# LC_LPF11.net
KiCad netlist of a schematic drawn in Altium Designer
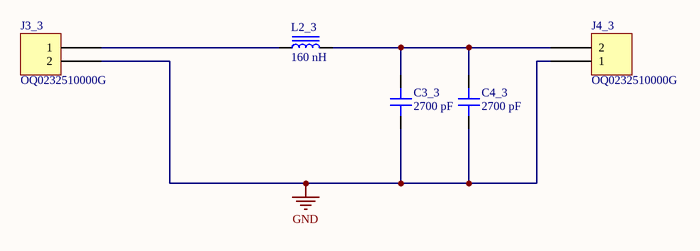
[diagram p0: LC_LPF11.SchDoc]

(export (version "E")
  (design (tool "Eeschema 10.0.6"))
  (components
    (comp (ref "C3_3")
      (value "2700 pF")
      (footprint "CAP 0603_1608")
      (description "CAP CER 2700PF 25V NP0 0603")
      (fields (field (name "PART NUMBER") "C0603C272F3GAC7867") (field (name "MANUFACTURER") "KEMET"))
      (libsource (lib "Celestial Altium Library - altium_library") (part "Capacitor"))
    )
    (comp (ref "C4_3")
      (value "2700 pF")
      (footprint "CAP 0603_1608")
      (description "CAP CER 2700PF 25V NP0 0603")
      (fields (field (name "PART NUMBER") "C0603C272F3GAC7867") (field (name "MANUFACTURER") "KEMET"))
      (libsource (lib "Celestial Altium Library - altium_library") (part "Capacitor"))
    )
    (comp (ref "J3_3")
      (value "OQ0232510000G")
      (footprint "FCI 06-381-2PIN")
      (description "TERM BLOCK HDR 2POS 90DEG 3.81MM")
      (fields (field (name "MANUFACTURER") "Amphenol Anytek"))
      (libsource (lib "Celestial Altium Library - altium_library") (part "2 Pin"))
    )
    (comp (ref "J4_3")
      (value "OQ0232510000G")
      (footprint "FCI 06-381-2PIN")
      (description "TERM BLOCK HDR 2POS 90DEG 3.81MM")
      (fields (field (name "MANUFACTURER") "Amphenol Anytek"))
      (libsource (lib "") (part "2 Pin_1"))
    )
    (comp (ref "L2_3")
      (value "160 nH")
      (footprint "IND 0402_1005 RF WW")
      (description "FIXED IND 160NH 480MA 330MOHM SM")
      (fields
        (field (name "PART NUMBER") "LQW15CNR16J00D")
        (field (name "MANUFACTURER") "Murata Electronics")
      )
      (libsource (lib "Celestial Altium Library - altium_library") (part "Inductor"))
    )
  )
  (nets
    (net (code "1") (name "GND") (class "Default")
      (node (ref "C3_3") (pin "1") (pinfunction "1_1") (pintype "passive"))
      (node (ref "C4_3") (pin "1") (pinfunction "1_1") (pintype "passive"))
      (node (ref "J3_3") (pin "2") (pinfunction "2_2") (pintype "passive"))
      (node (ref "J4_3") (pin "1") (pinfunction "1_1") (pintype "passive"))
    )
    (net (code "2") (name "Net-(C3_3-Pad2)") (class "Default")
      (node (ref "C3_3") (pin "2") (pinfunction "2_2") (pintype "passive"))
      (node (ref "C4_3") (pin "2") (pinfunction "2_2") (pintype "passive"))
      (node (ref "J4_3") (pin "2") (pinfunction "2_2") (pintype "passive"))
      (node (ref "L2_3") (pin "2") (pinfunction "2_2") (pintype "passive"))
    )
    (net (code "3") (name "Net-(J3_3-Pad1)") (class "Default")
      (node (ref "J3_3") (pin "1") (pinfunction "1_1") (pintype "passive"))
      (node (ref "L2_3") (pin "1") (pinfunction "1_1") (pintype "passive"))
    )
  )
)
